# AstableMultivibrator-PNP-alt.net
KiCad netlist of a schematic drawn in EAGLE
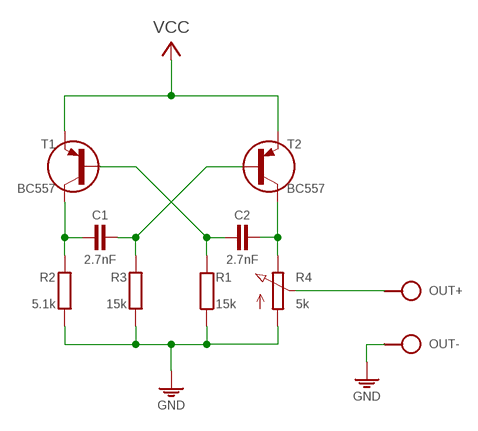
[diagram p0: schematic, sheet 1]

(export (version "E")
  (design (tool "Eeschema 10.0.6"))
  (components
    (comp (ref "C1")
      (value "2.7nF")
      (footprint "eagle-import:C0750-020X044")
      (libsource (lib "eagle-import") (part "C-H075-020X044"))
    )
    (comp (ref "C2")
      (value "2.7nF")
      (footprint "eagle-import:C0750-020X044")
      (libsource (lib "eagle-import") (part "C-H075-020X044"))
    )
    (comp (ref "J1")
      (value "VCC_GNDPWR-L")
      (footprint "eagle-import:PWR-L")
      (libsource (lib "eagle-import") (part "VCC_GNDPWR-L"))
    )
    (comp (ref "OUT")
      (value "SPAD+-+-")
      (footprint "eagle-import:SPAD+-")
      (libsource (lib "eagle-import") (part "SPAD+-+-"))
    )
    (comp (ref "R1")
      (value "15k")
      (footprint "eagle-import:0202_7-V")
      (libsource (lib "eagle-import") (part "R0202/7-V"))
    )
    (comp (ref "R2")
      (value "5.1k")
      (footprint "eagle-import:0202_7-V")
      (libsource (lib "eagle-import") (part "R0202/7-V"))
    )
    (comp (ref "R3")
      (value "15k")
      (footprint "eagle-import:0202_7-V")
      (libsource (lib "eagle-import") (part "R0202/7-V"))
    )
    (comp (ref "R4")
      (value "5k")
      (footprint "eagle-import:POT-V")
      (libsource (lib "eagle-import") (part "POT-V"))
    )
    (comp (ref "T1")
      (value "BC557")
      (footprint "eagle-import:TO92-CBE")
      (libsource (lib "eagle-import") (part "BC557CBE"))
    )
    (comp (ref "T2")
      (value "BC557")
      (footprint "eagle-import:TO92-CBE")
      (libsource (lib "eagle-import") (part "BC557CBE"))
    )
  )
  (nets
    (net (code "1") (name "GND") (class "Default")
      (node (ref "J1") (pin "1") (pinfunction "GND_1") (pintype "power_in"))
      (node (ref "OUT") (pin "1") (pinfunction "P$1_1") (pintype "passive"))
      (node (ref "R1") (pin "1") (pinfunction "2_1") (pintype "passive"))
      (node (ref "R2") (pin "1") (pinfunction "2_1") (pintype "passive"))
      (node (ref "R3") (pin "1") (pinfunction "2_1") (pintype "passive"))
      (node (ref "R4") (pin "A") (pinfunction "A_A") (pintype "passive"))
    )
    (net (code "2") (name "Net-(C2-Pad2)") (class "Default")
      (node (ref "C2") (pin "2") (pinfunction "2_2") (pintype "passive"))
      (node (ref "R4") (pin "E") (pinfunction "E_E") (pintype "passive"))
      (node (ref "T2") (pin "C") (pinfunction "C_C") (pintype "passive"))
    )
    (net (code "3") (name "Net-(J1A-VCC)") (class "Default")
      (node (ref "J1") (pin "2") (pinfunction "VCC_2") (pintype "power_in"))
      (node (ref "T1") (pin "E") (pinfunction "E_E") (pintype "passive"))
      (node (ref "T2") (pin "E") (pinfunction "E_E") (pintype "passive"))
    )
    (net (code "4") (name "Net-(OUTA-P$1)") (class "Default")
      (node (ref "OUT") (pin "2") (pinfunction "P$1_2") (pintype "passive"))
      (node (ref "R4") (pin "S") (pinfunction "S_S") (pintype "passive"))
    )
    (net (code "5") (name "Net-(R1-1)") (class "Default")
      (node (ref "C2") (pin "1") (pinfunction "1_1") (pintype "passive"))
      (node (ref "R1") (pin "2") (pinfunction "1_2") (pintype "passive"))
      (node (ref "T1") (pin "B") (pinfunction "B_B") (pintype "passive"))
    )
    (net (code "6") (name "Net-(R2-1)") (class "Default")
      (node (ref "C1") (pin "1") (pinfunction "1_1") (pintype "passive"))
      (node (ref "R2") (pin "2") (pinfunction "1_2") (pintype "passive"))
      (node (ref "T1") (pin "C") (pinfunction "C_C") (pintype "passive"))
    )
    (net (code "7") (name "Net-(R3-1)") (class "Default")
      (node (ref "C1") (pin "2") (pinfunction "2_2") (pintype "passive"))
      (node (ref "R3") (pin "2") (pinfunction "1_2") (pintype "passive"))
      (node (ref "T2") (pin "B") (pinfunction "B_B") (pintype "passive"))
    )
  )
)
